# Pressure_pump_V2_1.net
KiCad netlist of a schematic drawn in EAGLE
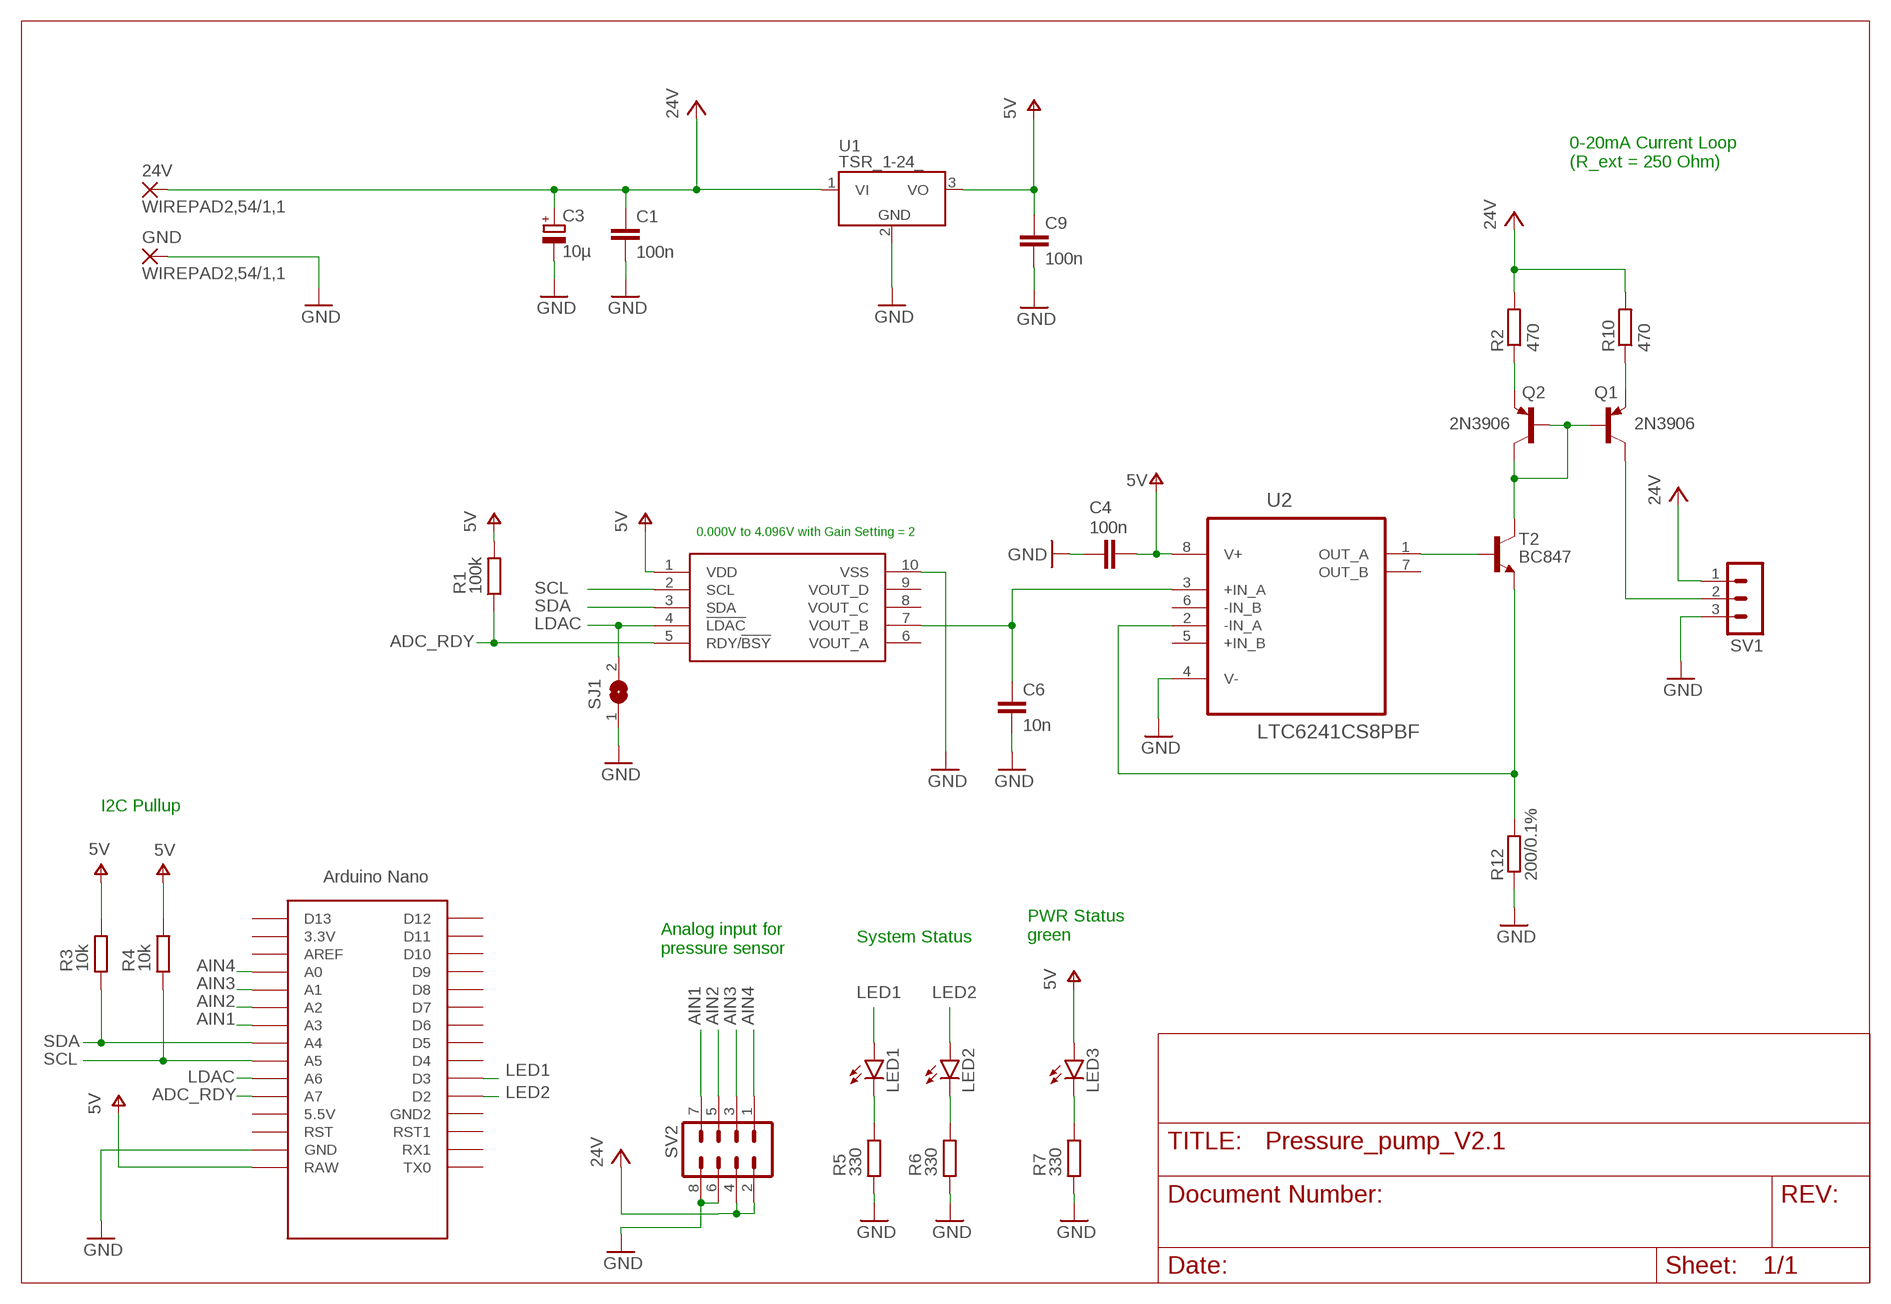
[diagram p0: schematic, sheet 1]

(export (version "E")
  (design (tool "Eeschema 10.0.6"))
  (components
    (comp (ref "24V")
      (value "WIREPAD2,54/1,1")
      (footprint "eagle-import:2,54_1,1")
      (libsource (lib "eagle-import") (part "WIREPAD2,54/1,1"))
    )
    (comp (ref "C1")
      (value "100n")
      (footprint "eagle-import:C0603")
      (libsource (lib "eagle-import") (part "C-EUC0603"))
    )
    (comp (ref "C3")
      (value "10µ")
      (footprint "eagle-import:153CLV-0810")
      (libsource (lib "eagle-import") (part "CPOL-EU153CLV-0810"))
    )
    (comp (ref "C4")
      (value "100n")
      (footprint "eagle-import:C0603")
      (libsource (lib "eagle-import") (part "C-EUC0603"))
    )
    (comp (ref "C6")
      (value "10n")
      (footprint "eagle-import:C0603")
      (libsource (lib "eagle-import") (part "C-EUC0603"))
    )
    (comp (ref "C9")
      (value "100n")
      (footprint "eagle-import:C0603")
      (libsource (lib "eagle-import") (part "C-EUC0603"))
    )
    (comp (ref "GND")
      (value "WIREPAD2,54/1,1")
      (footprint "eagle-import:2,54_1,1")
      (libsource (lib "eagle-import") (part "WIREPAD2,54/1,1"))
    )
    (comp (ref "LED1")
      (value "LED5MM")
      (footprint "eagle-import:LED5MM")
      (libsource (lib "eagle-import") (part "LED5MM"))
    )
    (comp (ref "LED2")
      (value "LED5MM")
      (footprint "eagle-import:LED5MM")
      (libsource (lib "eagle-import") (part "LED5MM"))
    )
    (comp (ref "LED3")
      (value "LED5MM")
      (footprint "eagle-import:LED5MM")
      (libsource (lib "eagle-import") (part "LED5MM"))
    )
    (comp (ref "Q1")
      (value "2N3906")
      (footprint "eagle-import:TO92")
      (libsource (lib "eagle-import") (part "2N3906"))
    )
    (comp (ref "Q2")
      (value "2N3906")
      (footprint "eagle-import:TO92")
      (libsource (lib "eagle-import") (part "2N3906"))
    )
    (comp (ref "R1")
      (value "100k")
      (footprint "eagle-import:R0603")
      (libsource (lib "eagle-import") (part "R-EU_R0603"))
    )
    (comp (ref "R2")
      (value "470")
      (footprint "eagle-import:R0603")
      (libsource (lib "eagle-import") (part "R-EU_R0603"))
    )
    (comp (ref "R3")
      (value "10k")
      (footprint "eagle-import:R0603")
      (libsource (lib "eagle-import") (part "R-EU_R0603"))
    )
    (comp (ref "R4")
      (value "10k")
      (footprint "eagle-import:R0603")
      (libsource (lib "eagle-import") (part "R-EU_R0603"))
    )
    (comp (ref "R5")
      (value "330")
      (footprint "eagle-import:R0603")
      (libsource (lib "eagle-import") (part "R-EU_R0603"))
    )
    (comp (ref "R6")
      (value "330")
      (footprint "eagle-import:R0603")
      (libsource (lib "eagle-import") (part "R-EU_R0603"))
    )
    (comp (ref "R7")
      (value "330")
      (footprint "eagle-import:R0603")
      (libsource (lib "eagle-import") (part "R-EU_R0603"))
    )
    (comp (ref "R10")
      (value "470")
      (footprint "eagle-import:R0603")
      (libsource (lib "eagle-import") (part "R-EU_R0603"))
    )
    (comp (ref "R12")
      (value "200/0.1%")
      (footprint "eagle-import:R0805")
      (libsource (lib "eagle-import") (part "R-EU_R0805"))
    )
    (comp (ref "SJ1") (value "SJ") (footprint "eagle-import:SJ") (libsource (lib "eagle-import") (part "SJ")))
    (comp (ref "SV1")
      (value "MA03-1")
      (footprint "eagle-import:MA03-1")
      (libsource (lib "eagle-import") (part "MA03-1"))
    )
    (comp (ref "SV2")
      (value "MA04-2")
      (footprint "eagle-import:MA04-2")
      (libsource (lib "eagle-import") (part "MA04-2"))
    )
    (comp (ref "T2")
      (value "BC847")
      (footprint "eagle-import:SOT23")
      (libsource (lib "eagle-import") (part "BC847"))
    )
    (comp (ref "U$1")
      (value "NANO")
      (footprint "eagle-import:NANO")
      (libsource (lib "eagle-import") (part "NANO"))
    )
    (comp (ref "U$2")
      (value "MCP4728")
      (footprint "eagle-import:MSOP10")
      (libsource (lib "eagle-import") (part "MCP4728"))
    )
    (comp (ref "U1")
      (value "TSR_1-24_")
      (footprint "eagle-import:TSR-1")
      (libsource (lib "eagle-import") (part "TSR_1-24_"))
    )
    (comp (ref "U2")
      (value "LTC6241CS8PBF")
      (footprint "eagle-import:SOIC127P600X175-8N")
      (fields (field (name "MPN") "LTC6241CS8#PBF"))
      (libsource (lib "eagle-import") (part "LTC6241CS8PBF"))
    )
  )
  (nets
    (net (code "1") (name "/ADC_RDY") (class "Default")
      (node (ref "R1") (pin "1") (pinfunction "1_1") (pintype "passive"))
      (node (ref "U$1") (pin "A7") (pinfunction "A7_A7") (pintype "bidirectional"))
      (node (ref "U$2") (pin "5") (pinfunction "RDY/~{BSY}_5") (pintype "bidirectional"))
    )
    (net (code "2") (name "/AIN1") (class "Default")
      (node (ref "SV2") (pin "7") (pinfunction "7_7") (pintype "passive"))
      (node (ref "U$1") (pin "A3") (pinfunction "A3_A3") (pintype "bidirectional"))
    )
    (net (code "3") (name "/AIN2") (class "Default")
      (node (ref "SV2") (pin "5") (pinfunction "5_5") (pintype "passive"))
      (node (ref "U$1") (pin "A2") (pinfunction "A2_A2") (pintype "bidirectional"))
    )
    (net (code "4") (name "/AIN3") (class "Default")
      (node (ref "SV2") (pin "3") (pinfunction "3_3") (pintype "passive"))
      (node (ref "U$1") (pin "A1") (pinfunction "A1_A1") (pintype "bidirectional"))
    )
    (net (code "5") (name "/AIN4") (class "Default")
      (node (ref "SV2") (pin "1") (pinfunction "1_1") (pintype "passive"))
      (node (ref "U$1") (pin "A0") (pinfunction "A0_A0") (pintype "bidirectional"))
    )
    (net (code "6") (name "/LDAC") (class "Default")
      (node (ref "SJ1") (pin "2") (pinfunction "2_2") (pintype "passive"))
      (node (ref "U$1") (pin "A6") (pinfunction "A6_A6") (pintype "bidirectional"))
      (node (ref "U$2") (pin "4") (pinfunction "~{LDAC}_4") (pintype "bidirectional"))
    )
    (net (code "7") (name "/LED1") (class "Default")
      (node (ref "LED1") (pin "A") (pinfunction "A_A") (pintype "passive"))
      (node (ref "U$1") (pin "D3") (pinfunction "D3_D3") (pintype "bidirectional"))
    )
    (net (code "8") (name "/LED2") (class "Default")
      (node (ref "LED2") (pin "A") (pinfunction "A_A") (pintype "passive"))
      (node (ref "U$1") (pin "D2") (pinfunction "D2_D2") (pintype "bidirectional"))
    )
    (net (code "9") (name "/SCL") (class "Default")
      (node (ref "R4") (pin "1") (pinfunction "1_1") (pintype "passive"))
      (node (ref "U$1") (pin "A5") (pinfunction "A5_A5") (pintype "bidirectional"))
      (node (ref "U$2") (pin "2") (pinfunction "SCL_2") (pintype "bidirectional"))
    )
    (net (code "10") (name "/SDA") (class "Default")
      (node (ref "R3") (pin "1") (pinfunction "1_1") (pintype "passive"))
      (node (ref "U$1") (pin "A4") (pinfunction "A4_A4") (pintype "bidirectional"))
      (node (ref "U$2") (pin "3") (pinfunction "SDA_3") (pintype "bidirectional"))
    )
    (net (code "11") (name "5V") (class "Default")
      (node (ref "C4") (pin "2") (pinfunction "2_2") (pintype "passive"))
      (node (ref "C9") (pin "1") (pinfunction "1_1") (pintype "passive"))
      (node (ref "LED3") (pin "A") (pinfunction "A_A") (pintype "passive"))
      (node (ref "R1") (pin "2") (pinfunction "2_2") (pintype "passive"))
      (node (ref "R3") (pin "2") (pinfunction "2_2") (pintype "passive"))
      (node (ref "R4") (pin "2") (pinfunction "2_2") (pintype "passive"))
      (node (ref "U$1") (pin "RAW") (pinfunction "RAW_RAW") (pintype "bidirectional"))
      (node (ref "U$2") (pin "1") (pinfunction "VDD_1") (pintype "bidirectional"))
      (node (ref "U1") (pin "3") (pinfunction "VO_3") (pintype "power_in"))
      (node (ref "U2") (pin "8") (pinfunction "V+_8") (pintype "power_in"))
    )
    (net (code "12") (name "24V") (class "Default")
      (node (ref "24V") (pin "1") (pinfunction "P_1") (pintype "passive"))
      (node (ref "C1") (pin "1") (pinfunction "1_1") (pintype "passive"))
      (node (ref "C3") (pin "+") (pinfunction "+_+") (pintype "passive"))
      (node (ref "R10") (pin "2") (pinfunction "2_2") (pintype "passive"))
      (node (ref "R2") (pin "2") (pinfunction "2_2") (pintype "passive"))
      (node (ref "SV1") (pin "1") (pinfunction "1_1") (pintype "passive"))
      (node (ref "SV2") (pin "2") (pinfunction "2_2") (pintype "passive"))
      (node (ref "SV2") (pin "4") (pinfunction "4_4") (pintype "passive"))
      (node (ref "U1") (pin "1") (pinfunction "VI_1") (pintype "power_in"))
    )
    (net (code "13") (name "GND") (class "Default")
      (node (ref "C1") (pin "2") (pinfunction "2_2") (pintype "passive"))
      (node (ref "C3") (pin "-") (pinfunction "-_-") (pintype "passive"))
      (node (ref "C4") (pin "1") (pinfunction "1_1") (pintype "passive"))
      (node (ref "C6") (pin "2") (pinfunction "2_2") (pintype "passive"))
      (node (ref "C9") (pin "2") (pinfunction "2_2") (pintype "passive"))
      (node (ref "GND") (pin "1") (pinfunction "P_1") (pintype "passive"))
      (node (ref "R12") (pin "1") (pinfunction "1_1") (pintype "passive"))
      (node (ref "R5") (pin "1") (pinfunction "1_1") (pintype "passive"))
      (node (ref "R6") (pin "1") (pinfunction "1_1") (pintype "passive"))
      (node (ref "R7") (pin "1") (pinfunction "1_1") (pintype "passive"))
      (node (ref "SJ1") (pin "1") (pinfunction "1_1") (pintype "passive"))
      (node (ref "SV1") (pin "3") (pinfunction "3_3") (pintype "passive"))
      (node (ref "SV2") (pin "6") (pinfunction "6_6") (pintype "passive"))
      (node (ref "SV2") (pin "8") (pinfunction "8_8") (pintype "passive"))
      (node (ref "U$1") (pin "GND") (pinfunction "GND_GND") (pintype "bidirectional"))
      (node (ref "U$2") (pin "10") (pinfunction "VSS_10") (pintype "bidirectional"))
      (node (ref "U1") (pin "2") (pinfunction "GND_2") (pintype "power_in"))
      (node (ref "U2") (pin "4") (pinfunction "V-_4") (pintype "power_in"))
    )
    (net (code "14") (name "Net-(LED1-C)") (class "Default")
      (node (ref "LED1") (pin "K") (pinfunction "C_K") (pintype "passive"))
      (node (ref "R5") (pin "2") (pinfunction "2_2") (pintype "passive"))
    )
    (net (code "15") (name "Net-(LED2-C)") (class "Default")
      (node (ref "LED2") (pin "K") (pinfunction "C_K") (pintype "passive"))
      (node (ref "R6") (pin "2") (pinfunction "2_2") (pintype "passive"))
    )
    (net (code "16") (name "Net-(LED3-C)") (class "Default")
      (node (ref "LED3") (pin "K") (pinfunction "C_K") (pintype "passive"))
      (node (ref "R7") (pin "2") (pinfunction "2_2") (pintype "passive"))
    )
    (net (code "17") (name "Net-(Q1-B)") (class "Default")
      (node (ref "Q1") (pin "2") (pinfunction "B_2") (pintype "passive"))
      (node (ref "Q2") (pin "1") (pinfunction "C_1") (pintype "passive"))
      (node (ref "Q2") (pin "2") (pinfunction "B_2") (pintype "passive"))
      (node (ref "T2") (pin "3") (pinfunction "C_3") (pintype "passive"))
    )
    (net (code "18") (name "Net-(Q1-C)") (class "Default")
      (node (ref "Q1") (pin "1") (pinfunction "C_1") (pintype "passive"))
      (node (ref "SV1") (pin "2") (pinfunction "2_2") (pintype "passive"))
    )
    (net (code "19") (name "Net-(Q1-E)") (class "Default")
      (node (ref "Q1") (pin "3") (pinfunction "E_3") (pintype "passive"))
      (node (ref "R10") (pin "1") (pinfunction "1_1") (pintype "passive"))
    )
    (net (code "20") (name "Net-(Q2-E)") (class "Default")
      (node (ref "Q2") (pin "3") (pinfunction "E_3") (pintype "passive"))
      (node (ref "R2") (pin "1") (pinfunction "1_1") (pintype "passive"))
    )
    (net (code "21") (name "Net-(T2-B)") (class "Default")
      (node (ref "T2") (pin "1") (pinfunction "B_1") (pintype "passive"))
      (node (ref "U2") (pin "1") (pinfunction "OUT_A_1") (pintype "output"))
    )
    (net (code "22") (name "Net-(T2-E)") (class "Default")
      (node (ref "R12") (pin "2") (pinfunction "2_2") (pintype "passive"))
      (node (ref "T2") (pin "2") (pinfunction "E_2") (pintype "passive"))
      (node (ref "U2") (pin "2") (pinfunction "-IN_A_2") (pintype "input"))
    )
    (net (code "23") (name "Net-(U$2-VOUT_B)") (class "Default")
      (node (ref "C6") (pin "1") (pinfunction "1_1") (pintype "passive"))
      (node (ref "U$2") (pin "7") (pinfunction "VOUT_B_7") (pintype "bidirectional"))
      (node (ref "U2") (pin "3") (pinfunction "+IN_A_3") (pintype "input"))
    )
    (net (code "24") (name "unconnected-(U$1-5.5V-Pad5V)") (class "Default")
      (node (ref "U$1") (pin "5V") (pinfunction "5.5V_5V") (pintype "bidirectional"))
    )
    (net (code "25") (name "unconnected-(U$1-GND2-PadGND1)") (class "Default")
      (node (ref "U$1") (pin "GND1") (pinfunction "GND2_GND1") (pintype "bidirectional"))
    )
    (net (code "26") (name "unconnected-(U$1-Pad3.3V)") (class "Default")
      (node (ref "U$1") (pin "3.3V") (pinfunction "3.3V_3.3V") (pintype "bidirectional"))
    )
    (net (code "27") (name "unconnected-(U$1-PadAREF)") (class "Default")
      (node (ref "U$1") (pin "AREF") (pinfunction "AREF_AREF") (pintype "bidirectional"))
    )
    (net (code "28") (name "unconnected-(U$1-PadD4)") (class "Default")
      (node (ref "U$1") (pin "D4") (pinfunction "D4_D4") (pintype "bidirectional"))
    )
    (net (code "29") (name "unconnected-(U$1-PadD5)") (class "Default")
      (node (ref "U$1") (pin "D5") (pinfunction "D5_D5") (pintype "bidirectional"))
    )
    (net (code "30") (name "unconnected-(U$1-PadD6)") (class "Default")
      (node (ref "U$1") (pin "D6") (pinfunction "D6_D6") (pintype "bidirectional"))
    )
    (net (code "31") (name "unconnected-(U$1-PadD7)") (class "Default")
      (node (ref "U$1") (pin "D7") (pinfunction "D7_D7") (pintype "bidirectional"))
    )
    (net (code "32") (name "unconnected-(U$1-PadD8)") (class "Default")
      (node (ref "U$1") (pin "D8") (pinfunction "D8_D8") (pintype "bidirectional"))
    )
    (net (code "33") (name "unconnected-(U$1-PadD9)") (class "Default")
      (node (ref "U$1") (pin "D9") (pinfunction "D9_D9") (pintype "bidirectional"))
    )
    (net (code "34") (name "unconnected-(U$1-PadD10)") (class "Default")
      (node (ref "U$1") (pin "D10") (pinfunction "D10_D10") (pintype "bidirectional"))
    )
    (net (code "35") (name "unconnected-(U$1-PadD11)") (class "Default")
      (node (ref "U$1") (pin "D11") (pinfunction "D11_D11") (pintype "bidirectional"))
    )
    (net (code "36") (name "unconnected-(U$1-PadD12)") (class "Default")
      (node (ref "U$1") (pin "D12") (pinfunction "D12_D12") (pintype "bidirectional"))
    )
    (net (code "37") (name "unconnected-(U$1-PadD13)") (class "Default")
      (node (ref "U$1") (pin "D13") (pinfunction "D13_D13") (pintype "bidirectional"))
    )
    (net (code "38") (name "unconnected-(U$1-PadICSP1)") (class "Default")
      (node (ref "U$1") (pin "ICSP1") (pinfunction "ICSP1_ICSP1") (pintype "bidirectional"))
    )
    (net (code "39") (name "unconnected-(U$1-PadICSP2)") (class "Default")
      (node (ref "U$1") (pin "ICSP2") (pinfunction "ICSP2_ICSP2") (pintype "bidirectional"))
    )
    (net (code "40") (name "unconnected-(U$1-PadICSP3)") (class "Default")
      (node (ref "U$1") (pin "ICSP3") (pinfunction "ICSP3_ICSP3") (pintype "bidirectional"))
    )
    (net (code "41") (name "unconnected-(U$1-PadICSP4)") (class "Default")
      (node (ref "U$1") (pin "ICSP4") (pinfunction "ICSP4_ICSP4") (pintype "bidirectional"))
    )
    (net (code "42") (name "unconnected-(U$1-PadICSP5)") (class "Default")
      (node (ref "U$1") (pin "ICSP5") (pinfunction "ICSP5_ICSP5") (pintype "bidirectional"))
    )
    (net (code "43") (name "unconnected-(U$1-PadICSP6)") (class "Default")
      (node (ref "U$1") (pin "ICSP6") (pinfunction "ICSP6_ICSP6") (pintype "bidirectional"))
    )
    (net (code "44") (name "unconnected-(U$1-PadRST)") (class "Default")
      (node (ref "U$1") (pin "RST") (pinfunction "RST_RST") (pintype "bidirectional"))
    )
    (net (code "45") (name "unconnected-(U$1-PadRST1)") (class "Default")
      (node (ref "U$1") (pin "RST1") (pinfunction "RST1_RST1") (pintype "bidirectional"))
    )
    (net (code "46") (name "unconnected-(U$1-PadRX1)") (class "Default")
      (node (ref "U$1") (pin "RX1") (pinfunction "RX1_RX1") (pintype "bidirectional"))
    )
    (net (code "47") (name "unconnected-(U$1-PadTX0)") (class "Default")
      (node (ref "U$1") (pin "TX0") (pinfunction "TX0_TX0") (pintype "bidirectional"))
    )
    (net (code "48") (name "unconnected-(U$2-VOUT_A-Pad6)") (class "Default")
      (node (ref "U$2") (pin "6") (pinfunction "VOUT_A_6") (pintype "bidirectional"))
    )
    (net (code "49") (name "unconnected-(U$2-VOUT_C-Pad8)") (class "Default")
      (node (ref "U$2") (pin "8") (pinfunction "VOUT_C_8") (pintype "bidirectional"))
    )
    (net (code "50") (name "unconnected-(U$2-VOUT_D-Pad9)") (class "Default")
      (node (ref "U$2") (pin "9") (pinfunction "VOUT_D_9") (pintype "bidirectional"))
    )
    (net (code "51") (name "unconnected-(U2-+IN_B-Pad5)") (class "Default")
      (node (ref "U2") (pin "5") (pinfunction "+IN_B_5") (pintype "input"))
    )
    (net (code "52") (name "unconnected-(U2--IN_B-Pad6)") (class "Default")
      (node (ref "U2") (pin "6") (pinfunction "-IN_B_6") (pintype "input"))
    )
    (net (code "53") (name "unconnected-(U2-OUT_B-Pad7)") (class "Default")
      (node (ref "U2") (pin "7") (pinfunction "OUT_B_7") (pintype "output"))
    )
  )
)
